# Versterker.net
KiCad netlist of a schematic drawn in Altium Designer
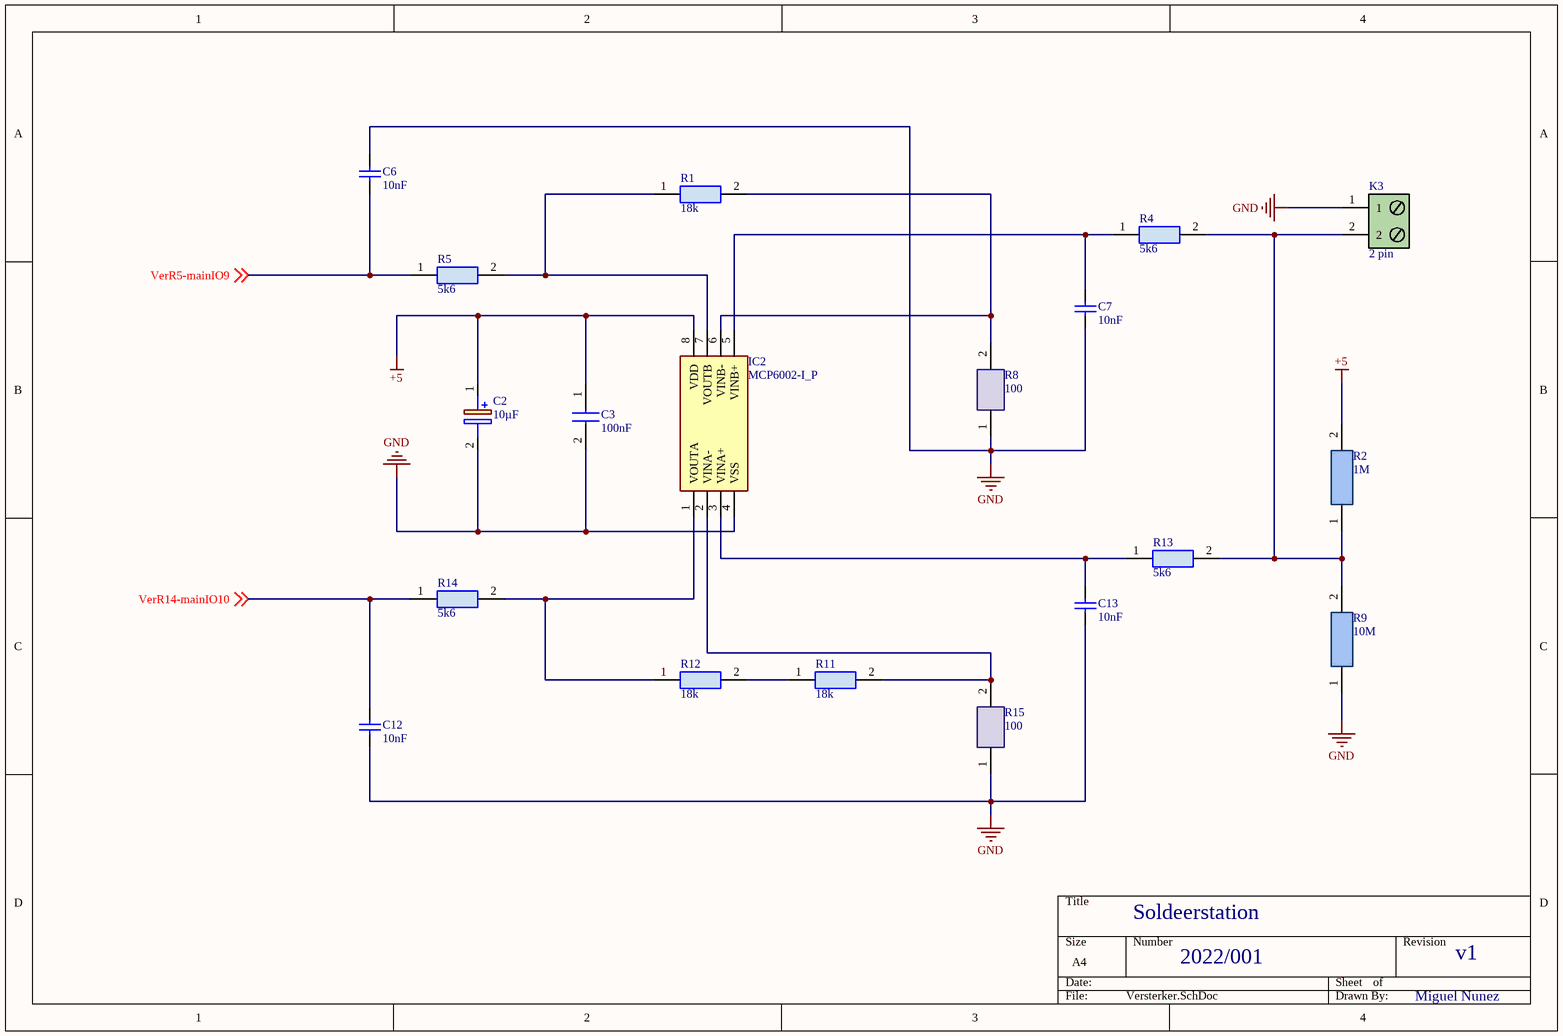
[diagram p0: Versterker.SchDoc]

(export (version "E")
  (design (tool "Eeschema 10.0.6"))
  (components
    (comp (ref "C2")
      (value "10µF")
      (footprint "WCAP-AT1H_D5H11")
      (description "Capacitor Polarised Wurth Elektronik 860240672002 10µF")
      (fields (field (name "MANUFACTURER_PART_NUMBER") "860240672002"))
      (libsource (lib "PO_SS_Lib") (part "ELCAP 10µF"))
    )
    (comp (ref "C3")
      (value "100nF")
      (footprint "WCAP-CSGP_0805_L2W1.25H0.8_Reflow")
      (description "Capacitor C0805C104K8RACAUTO")
      (fields (field (name "MANUFACTURER_PART_NUMBER") "C0805C104K8RACAUTO"))
      (libsource (lib "PO_SS_Lib") (part "CAP 0.1µF (100nF)"))
    )
    (comp (ref "C6")
      (value "10nF")
      (footprint "WCAP-CSGP_0805_L2W1.25H0.8_Reflow")
      (fields
        (field (name "MANUFACTURER") "Wurth Elektronik")
        (field (name "MANUFACTURER PART NUMBER") "885012207092")
      )
      (libsource (lib "PO_SS_Lib") (part "CAP 0.01µF WE"))
    )
    (comp (ref "C7")
      (value "10nF")
      (footprint "WCAP-CSGP_0805_L2W1.25H0.8_Reflow")
      (fields
        (field (name "MANUFACTURER") "Wurth Elektronik")
        (field (name "MANUFACTURER PART NUMBER") "885012207092")
      )
      (libsource (lib "PO_SS_Lib") (part "CAP 0.01µF WE"))
    )
    (comp (ref "C12")
      (value "10nF")
      (footprint "WCAP-CSGP_0805_L2W1.25H0.8_Reflow")
      (fields
        (field (name "MANUFACTURER") "Wurth Elektronik")
        (field (name "MANUFACTURER PART NUMBER") "885012207092")
      )
      (libsource (lib "PO_SS_Lib") (part "CAP 0.01µF WE"))
    )
    (comp (ref "C13")
      (value "10nF")
      (footprint "WCAP-CSGP_0805_L2W1.25H0.8_Reflow")
      (fields
        (field (name "MANUFACTURER") "Wurth Elektronik")
        (field (name "MANUFACTURER PART NUMBER") "885012207092")
      )
      (libsource (lib "PO_SS_Lib") (part "CAP 0.01µF WE"))
    )
    (comp (ref "IC2")
      (value "MCP6002-I_P")
      (footprint "SamacSys:DIP781W56P254L950H533Q8N")
      (description "Integrated Circuit Dual OPAMP MCP6002-I/P")
      (fields
        (field (name "MOUSER2 PART NUMBER") "579-MCP6002-I/P")
        (field (name "MANUFACTURER_PART_NUMBER") "MCP6002-I/P")
      )
      (libsource (lib "PO_SS_Lib") (part "MCP6002-I_P"))
    )
    (comp (ref "K3")
      (value "2 pin")
      (footprint "SamacSys:1729128")
      (description "Connector Term. blok. 1729128 2 pin")
      (fields (field (name "MANUFACTURER_PART_NUMBER") "1729128"))
      (libsource (lib "PO_SS_Lib") (part "Term. blok 2 pin"))
    )
    (comp (ref "R1")
      (value "18k")
      (footprint "RESC2012X60N")
      (description "18kΩ ±0.5% 0.1W 1/10W Chip Resistor 0805 (2012 Metric) Thin Film  RR1220P-183-D")
      (fields (field (name "TOLERANCE") "0.5%"))
      (libsource (lib "PO_SS_Lib") (part "RES 18k 0805"))
    )
    (comp (ref "R2")
      (value "1M")
      (footprint "RESC3115X65N")
      (description "Res Thin Film 1206 1M0Ω 0.1% 0.25W 15ppm/°C Molded SMD")
      (fields
        (field (name "MANUFACTURER") "TE Connectivity")
        (field (name "OCTOPART") "https://octopart.com/rp73d2b1m0btdf-te+connectivity-22741454")
      )
      (libsource (lib "PO_SS_Lib") (part "RES 1M 1206"))
    )
    (comp (ref "R4")
      (value "5k6")
      (footprint "SamacSys:RESC2012X50N")
      (description "5k6 SMD 0805  CRCW08055K60JNEA")
      (fields (field (name "MANUFACTURER_PART_NUMBER") "CRCW08055K60JNEA"))
      (libsource (lib "PO_SS_Lib") (part "RES 5k6 0805"))
    )
    (comp (ref "R5")
      (value "5k6")
      (footprint "SamacSys:RESC2012X50N")
      (description "5k6 SMD 0805  CRCW08055K60JNEA")
      (fields (field (name "MANUFACTURER_PART_NUMBER") "CRCW08055K60JNEA"))
      (libsource (lib "PO_SS_Lib") (part "RES 5k6 0805"))
    )
    (comp (ref "R8")
      (value "100")
      (footprint "SamacSys:RESC1220X65N")
      (description "100 Ohm SMD 0508  LTR10EZPJ101")
      (fields
        (field (name "MOUSER2 PART NUMBER") "755-LTR10EZPJ101")
        (field (name "MANUFACTURER_PART_NUMBER") "LTR10EZPJ101")
      )
      (libsource (lib "PO_SS_Lib") (part "RES 100 0508"))
    )
    (comp (ref "R9")
      (value "10M")
      (footprint "RESC3115X65N")
      (description "Res Thin Film 1206 1M0Ω 0.1% 0.25W 15ppm/°C Molded SMD  1206 10M 5% 0.25W TCR200")
      (fields
        (field (name "MANUFACTURER") "TE Connectivity")
        (field (name "OCTOPART") "https://octopart.com/rp73d2b1m0btdf-te+connectivity-22741454")
      )
      (libsource (lib "PO_SS_Lib") (part "RES 10M 1206"))
    )
    (comp (ref "R11")
      (value "18k")
      (footprint "RESC2012X60N")
      (description "18kΩ ±0.5% 0.1W 1/10W Chip Resistor 0805 (2012 Metric) Thin Film  RR1220P-183-D")
      (fields (field (name "TOLERANCE") "0.5%"))
      (libsource (lib "PO_SS_Lib") (part "RES 18k 0805"))
    )
    (comp (ref "R12")
      (value "18k")
      (footprint "RESC2012X60N")
      (description "18kΩ ±0.5% 0.1W 1/10W Chip Resistor 0805 (2012 Metric) Thin Film  RR1220P-183-D")
      (fields (field (name "TOLERANCE") "0.5%"))
      (libsource (lib "PO_SS_Lib") (part "RES 18k 0805"))
    )
    (comp (ref "R13")
      (value "5k6")
      (footprint "SamacSys:RESC2012X50N")
      (description "5k6 SMD 0805  CRCW08055K60JNEA")
      (fields (field (name "MANUFACTURER_PART_NUMBER") "CRCW08055K60JNEA"))
      (libsource (lib "PO_SS_Lib") (part "RES 5k6 0805"))
    )
    (comp (ref "R14")
      (value "5k6")
      (footprint "SamacSys:RESC2012X50N")
      (description "5k6 SMD 0805  CRCW08055K60JNEA")
      (fields (field (name "MANUFACTURER_PART_NUMBER") "CRCW08055K60JNEA"))
      (libsource (lib "PO_SS_Lib") (part "RES 5k6 0805"))
    )
    (comp (ref "R15")
      (value "100")
      (footprint "SamacSys:RESC1220X65N")
      (description "100 Ohm SMD 0508  LTR10EZPJ101")
      (fields
        (field (name "MOUSER2 PART NUMBER") "755-LTR10EZPJ101")
        (field (name "MANUFACTURER_PART_NUMBER") "LTR10EZPJ101")
      )
      (libsource (lib "PO_SS_Lib") (part "RES 100 0508"))
    )
  )
  (nets
    (net (code "1") (name "+5") (class "Default")
      (node (ref "C2") (pin "1") (pinfunction "+_1") (pintype "passive"))
      (node (ref "C3") (pin "1") (pinfunction "1_1") (pintype "passive"))
      (node (ref "IC2") (pin "8") (pinfunction "VDD_8") (pintype "passive"))
      (node (ref "R2") (pin "2") (pinfunction "2_2") (pintype "passive"))
    )
    (net (code "2") (name "GND") (class "Default")
      (node (ref "C12") (pin "1") (pinfunction "1_1") (pintype "passive"))
      (node (ref "C13") (pin "1") (pinfunction "1_1") (pintype "passive"))
      (node (ref "C2") (pin "2") (pinfunction "-_2") (pintype "passive"))
      (node (ref "C3") (pin "2") (pinfunction "2_2") (pintype "passive"))
      (node (ref "C6") (pin "2") (pinfunction "2_2") (pintype "passive"))
      (node (ref "C7") (pin "1") (pinfunction "1_1") (pintype "passive"))
      (node (ref "IC2") (pin "4") (pinfunction "VSS_4") (pintype "passive"))
      (node (ref "K3") (pin "1") (pinfunction "1_1") (pintype "passive"))
      (node (ref "R15") (pin "1") (pinfunction "1_1") (pintype "passive"))
      (node (ref "R8") (pin "1") (pinfunction "1_1") (pintype "passive"))
      (node (ref "R9") (pin "1") (pinfunction "1_1") (pintype "passive"))
    )
    (net (code "3") (name "Net-(IC2-VINA+)") (class "Default")
      (node (ref "C13") (pin "2") (pinfunction "2_2") (pintype "passive"))
      (node (ref "IC2") (pin "3") (pinfunction "VINA+_3") (pintype "passive"))
      (node (ref "R13") (pin "1") (pinfunction "1_1") (pintype "passive"))
    )
    (net (code "4") (name "Net-(IC2-VINA-)") (class "Default")
      (node (ref "IC2") (pin "2") (pinfunction "VINA-_2") (pintype "passive"))
      (node (ref "R11") (pin "2") (pinfunction "2_2") (pintype "passive"))
      (node (ref "R15") (pin "2") (pinfunction "2_2") (pintype "passive"))
    )
    (net (code "5") (name "Net-(IC2-VINB+)") (class "Default")
      (node (ref "C7") (pin "2") (pinfunction "2_2") (pintype "passive"))
      (node (ref "IC2") (pin "5") (pinfunction "VINB+_5") (pintype "passive"))
      (node (ref "R4") (pin "1") (pinfunction "1_1") (pintype "passive"))
    )
    (net (code "6") (name "Net-(IC2-VINB-)") (class "Default")
      (node (ref "IC2") (pin "6") (pinfunction "VINB-_6") (pintype "passive"))
      (node (ref "R1") (pin "2") (pinfunction "2_2") (pintype "passive"))
      (node (ref "R8") (pin "2") (pinfunction "2_2") (pintype "passive"))
    )
    (net (code "7") (name "Net-(IC2-VOUTA)") (class "Default")
      (node (ref "IC2") (pin "1") (pinfunction "VOUTA_1") (pintype "passive"))
      (node (ref "R12") (pin "1") (pinfunction "1_1") (pintype "passive"))
      (node (ref "R14") (pin "2") (pinfunction "2_2") (pintype "passive"))
    )
    (net (code "8") (name "Net-(IC2-VOUTB)") (class "Default")
      (node (ref "IC2") (pin "7") (pinfunction "VOUTB_7") (pintype "passive"))
      (node (ref "R1") (pin "1") (pinfunction "1_1") (pintype "passive"))
      (node (ref "R5") (pin "2") (pinfunction "2_2") (pintype "passive"))
    )
    (net (code "9") (name "Net-(K3-Pad2)") (class "Default")
      (node (ref "K3") (pin "2") (pinfunction "2_2") (pintype "passive"))
      (node (ref "R13") (pin "2") (pinfunction "2_2") (pintype "passive"))
      (node (ref "R2") (pin "1") (pinfunction "1_1") (pintype "passive"))
      (node (ref "R4") (pin "2") (pinfunction "2_2") (pintype "passive"))
      (node (ref "R9") (pin "2") (pinfunction "2_2") (pintype "passive"))
    )
    (net (code "10") (name "Net-(R11-Pad1)") (class "Default")
      (node (ref "R11") (pin "1") (pinfunction "1_1") (pintype "passive"))
      (node (ref "R12") (pin "2") (pinfunction "2_2") (pintype "passive"))
    )
    (net (code "11") (name "VerR5-mainIO9") (class "Default")
      (node (ref "C6") (pin "1") (pinfunction "1_1") (pintype "passive"))
      (node (ref "R5") (pin "1") (pinfunction "1_1") (pintype "passive"))
    )
    (net (code "12") (name "VerR14-mainIO10") (class "Default")
      (node (ref "C12") (pin "2") (pinfunction "2_2") (pintype "passive"))
      (node (ref "R14") (pin "1") (pinfunction "1_1") (pintype "passive"))
    )
  )
)
